# packmonitor.net
KiCad netlist of a schematic drawn in EAGLE
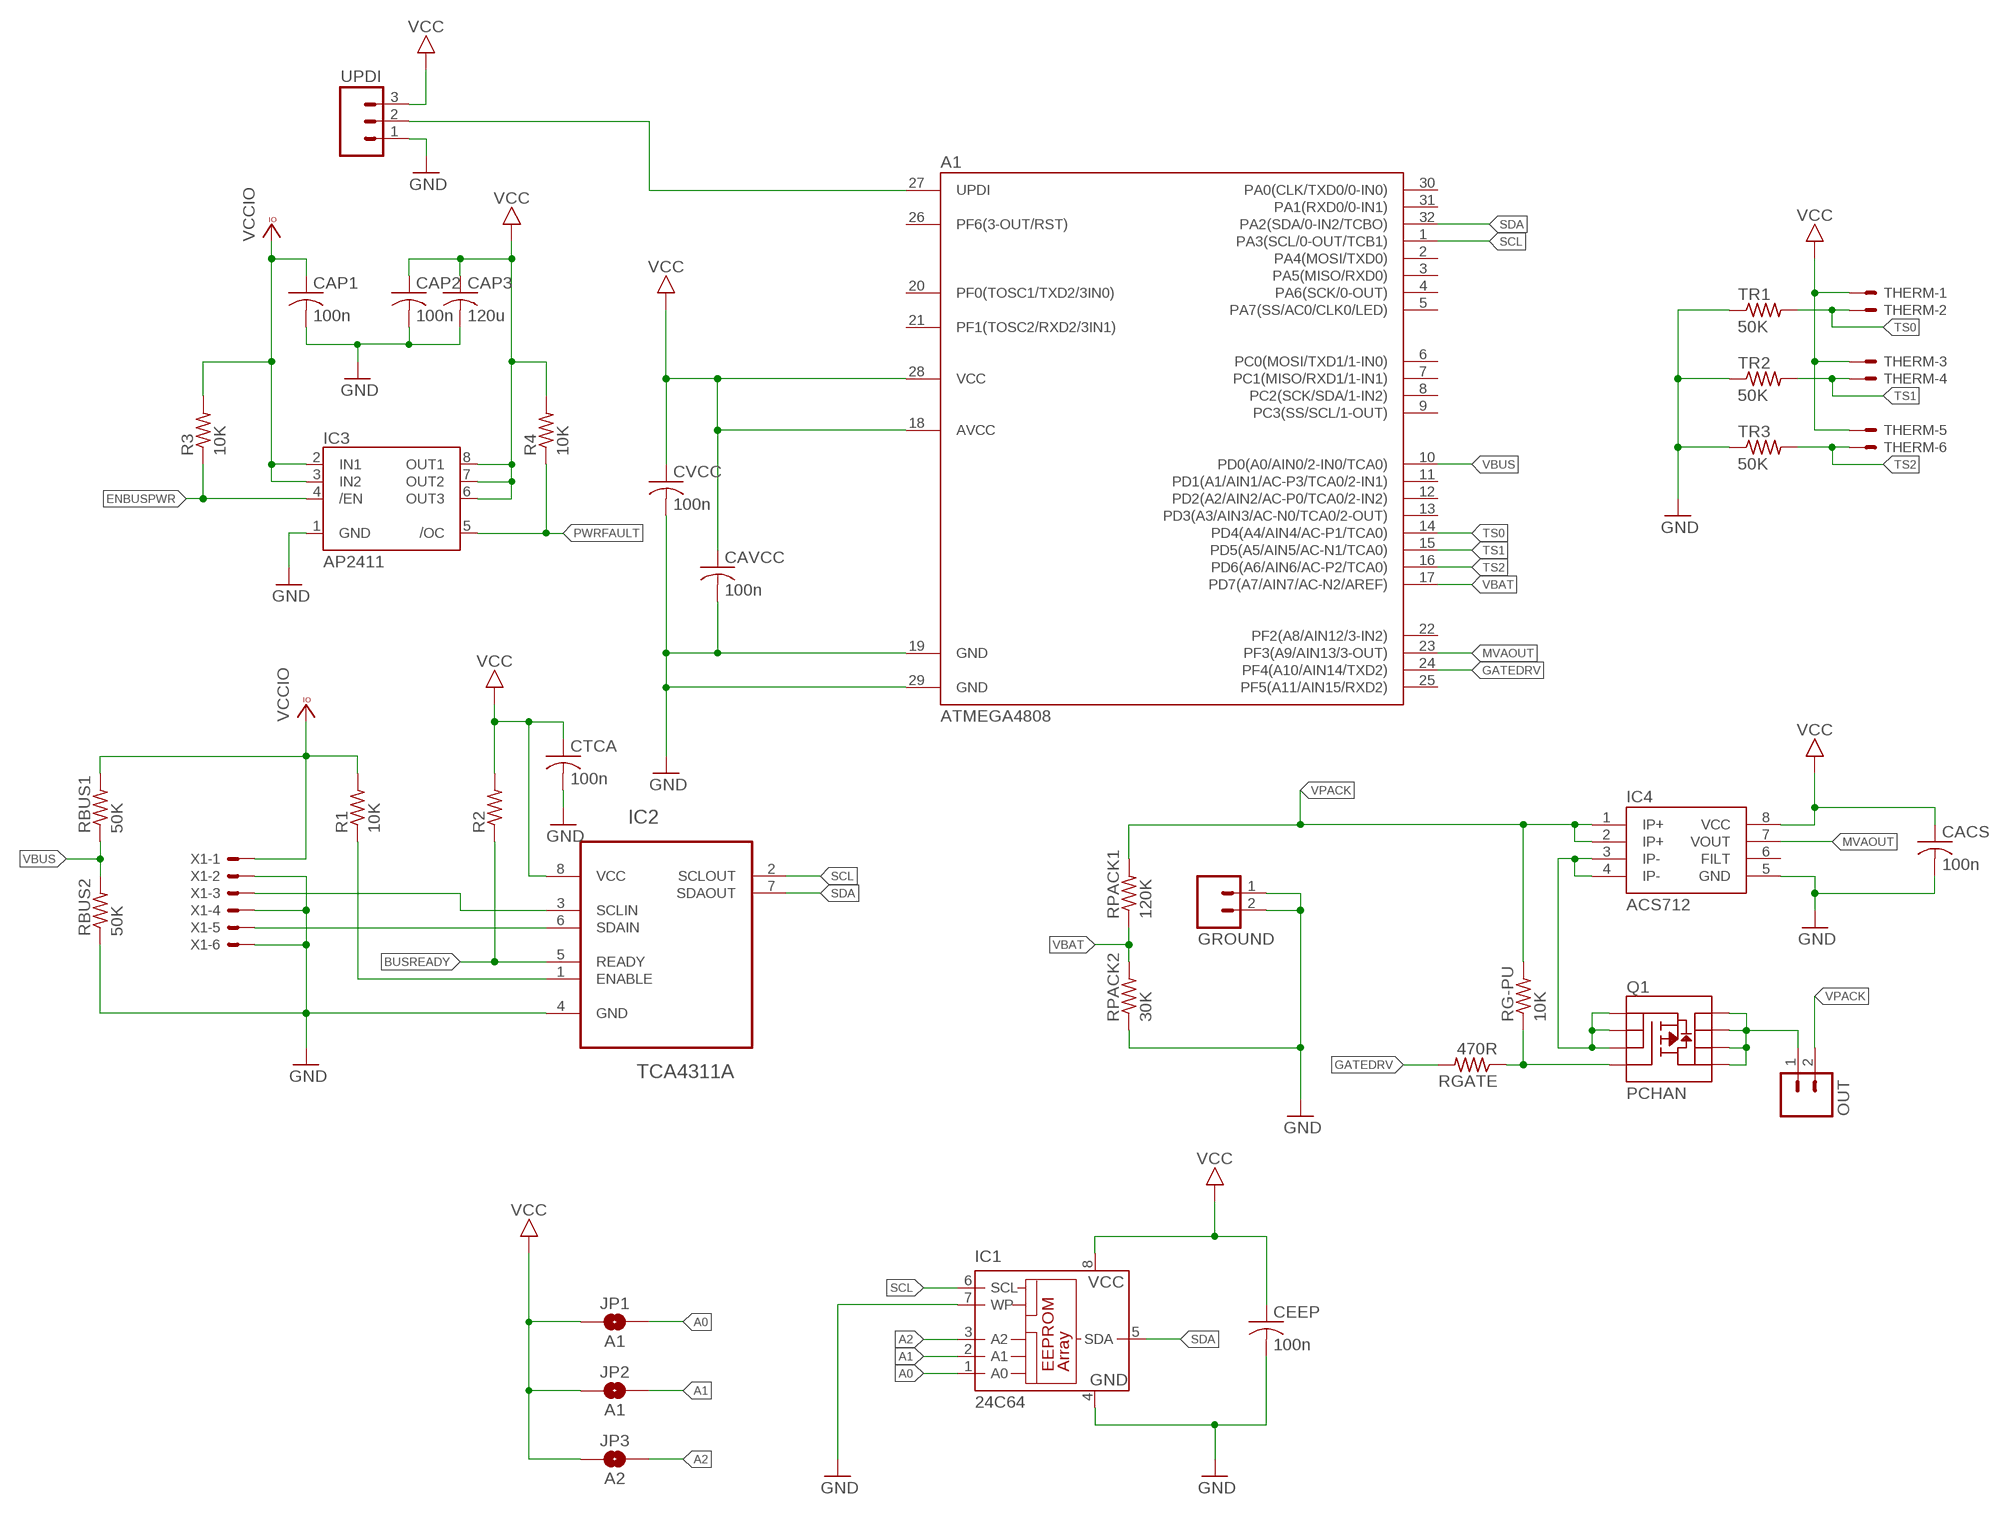
[diagram p0: schematic, sheet 1]

(export (version "E")
  (design (tool "Eeschema 10.0.6"))
  (components
    (comp (ref "A1")
      (value "ATMEGA4808")
      (footprint "eagle-import:TQFP32-08")
      (libsource (lib "eagle-import") (part "ATMEGA4808-TQFN32A"))
    )
    (comp (ref "CACS")
      (value "100n")
      (footprint "eagle-import:C0603")
      (libsource (lib "eagle-import") (part "C-USC0603"))
    )
    (comp (ref "CAP1")
      (value "100n")
      (footprint "eagle-import:C0603")
      (libsource (lib "eagle-import") (part "C-USC0603"))
    )
    (comp (ref "CAP2")
      (value "100n")
      (footprint "eagle-import:C0603")
      (libsource (lib "eagle-import") (part "C-USC0603"))
    )
    (comp (ref "CAP3")
      (value "120u")
      (footprint "eagle-import:C1206")
      (libsource (lib "eagle-import") (part "C-USC1206"))
    )
    (comp (ref "CAVCC")
      (value "100n")
      (footprint "eagle-import:C0603")
      (libsource (lib "eagle-import") (part "C-USC0603"))
    )
    (comp (ref "CEEP")
      (value "100n")
      (footprint "eagle-import:C0603")
      (libsource (lib "eagle-import") (part "C-USC0603"))
    )
    (comp (ref "CTCA")
      (value "100n")
      (footprint "eagle-import:C0603")
      (libsource (lib "eagle-import") (part "C-USC0603"))
    )
    (comp (ref "CVCC")
      (value "100n")
      (footprint "eagle-import:C0603")
      (libsource (lib "eagle-import") (part "C-USC0603"))
    )
    (comp (ref "GROUND")
      (value "M023.5MM")
      (footprint "eagle-import:SCREWTERMINAL-3.5MM-2")
      (libsource (lib "eagle-import") (part "M023.5MM"))
    )
    (comp (ref "IC1")
      (value "24C64")
      (footprint "eagle-import:SO-08")
      (libsource (lib "eagle-import") (part "24CSN04C"))
    )
    (comp (ref "IC2")
      (value "TCA4311A")
      (footprint "eagle-import:SOIC127P600X175-8N")
      (fields (field (name "MPN") "PCA9511AD,118"))
      (libsource (lib "eagle-import") (part "PCA9511AD,118"))
    )
    (comp (ref "IC3")
      (value "AP2411")
      (footprint "eagle-import:SO08")
      (libsource (lib "eagle-import") (part "TPS2041BD"))
    )
    (comp (ref "IC4")
      (value "ACS712")
      (footprint "eagle-import:SO08")
      (libsource (lib "eagle-import") (part "ACS712"))
    )
    (comp (ref "JP1")
      (value "A1")
      (footprint "eagle-import:SMT-JUMPER_2_NO_SILK")
      (libsource (lib "eagle-import") (part "JUMPER-SMT_2_NO_SILK"))
    )
    (comp (ref "JP2")
      (value "A1")
      (footprint "eagle-import:SMT-JUMPER_2_NO_SILK")
      (libsource (lib "eagle-import") (part "JUMPER-SMT_2_NO_SILK"))
    )
    (comp (ref "JP3")
      (value "A2")
      (footprint "eagle-import:SMT-JUMPER_2_NO_SILK")
      (libsource (lib "eagle-import") (part "JUMPER-SMT_2_NO_SILK"))
    )
    (comp (ref "OUT")
      (value "M023.5MM")
      (footprint "eagle-import:SCREWTERMINAL-3.5MM-2")
      (libsource (lib "eagle-import") (part "M023.5MM"))
    )
    (comp (ref "Q1")
      (value "PCHAN")
      (footprint "eagle-import:SO08")
      (libsource (lib "eagle-import") (part "MOSFET-PCHANNEL-SOIC8SOIC8"))
    )
    (comp (ref "R1")
      (value "10K")
      (footprint "eagle-import:R0603")
      (libsource (lib "eagle-import") (part "R-US_R0603"))
    )
    (comp (ref "R2")
      (value "R-US_R0603")
      (footprint "eagle-import:R0603")
      (libsource (lib "eagle-import") (part "R-US_R0603"))
    )
    (comp (ref "R3")
      (value "10K")
      (footprint "eagle-import:R0603")
      (libsource (lib "eagle-import") (part "R-US_R0603"))
    )
    (comp (ref "R4")
      (value "10K")
      (footprint "eagle-import:R0603")
      (libsource (lib "eagle-import") (part "R-US_R0603"))
    )
    (comp (ref "RBUS1")
      (value "50K")
      (footprint "eagle-import:R0805")
      (libsource (lib "eagle-import") (part "R-US_R0805"))
    )
    (comp (ref "RBUS2")
      (value "50K")
      (footprint "eagle-import:R0805")
      (libsource (lib "eagle-import") (part "R-US_R0805"))
    )
    (comp (ref "RG-PU")
      (value "10K")
      (footprint "eagle-import:R0603")
      (libsource (lib "eagle-import") (part "R-US_R0603"))
    )
    (comp (ref "RGATE")
      (value "470R")
      (footprint "eagle-import:R0603")
      (libsource (lib "eagle-import") (part "R-US_R0603"))
    )
    (comp (ref "RPACK1")
      (value "120K")
      (footprint "eagle-import:R0805")
      (libsource (lib "eagle-import") (part "R-US_R0805"))
    )
    (comp (ref "RPACK2")
      (value "30K")
      (footprint "eagle-import:R0805")
      (libsource (lib "eagle-import") (part "R-US_R0805"))
    )
    (comp (ref "THERM")
      (value "JST-XH-06-PIN-ROUND-PAD")
      (footprint "eagle-import:JST-XH-06-PACKAGE-ROUND-PAD")
      (libsource (lib "eagle-import") (part "JST-XH-06-PIN-ROUND-PAD"))
    )
    (comp (ref "TR1")
      (value "50K")
      (footprint "eagle-import:R0805")
      (libsource (lib "eagle-import") (part "R-US_R0805"))
    )
    (comp (ref "TR2")
      (value "50K")
      (footprint "eagle-import:R0805")
      (libsource (lib "eagle-import") (part "R-US_R0805"))
    )
    (comp (ref "TR3")
      (value "50K")
      (footprint "eagle-import:R0805")
      (libsource (lib "eagle-import") (part "R-US_R0805"))
    )
    (comp (ref "UPDI")
      (value "M03PTH")
      (footprint "eagle-import:1X03")
      (libsource (lib "eagle-import") (part "M03PTH"))
    )
    (comp (ref "X1")
      (value "JST-XH-06-PIN-LONG-PAD")
      (footprint "eagle-import:JST-XH-06-PACKAGE-LONG-PAD")
      (libsource (lib "eagle-import") (part "JST-XH-06-PIN-LONG-PAD"))
    )
  )
  (nets
    (net (code "1") (name "A0") (class "Default")
      (node (ref "IC1") (pin "1") (pinfunction "A0_1") (pintype "input"))
      (node (ref "JP1") (pin "2") (pinfunction "2_2") (pintype "passive"))
    )
    (net (code "2") (name "A1") (class "Default")
      (node (ref "IC1") (pin "2") (pinfunction "A1_2") (pintype "input"))
      (node (ref "JP2") (pin "2") (pinfunction "2_2") (pintype "passive"))
    )
    (net (code "3") (name "A2") (class "Default")
      (node (ref "IC1") (pin "3") (pinfunction "A2_3") (pintype "input"))
      (node (ref "JP3") (pin "2") (pinfunction "2_2") (pintype "passive"))
    )
    (net (code "4") (name "BUSREADY") (class "Default")
      (node (ref "IC2") (pin "5") (pinfunction "READY_5") (pintype "input"))
      (node (ref "R2") (pin "1") (pinfunction "1_1") (pintype "passive"))
    )
    (net (code "5") (name "ENBUSPWR") (class "Default")
      (node (ref "IC3") (pin "4") (pinfunction "/EN_4") (pintype "input"))
      (node (ref "R3") (pin "1") (pinfunction "1_1") (pintype "passive"))
    )
    (net (code "6") (name "GATEDRV") (class "Default")
      (node (ref "A1") (pin "24") (pinfunction "PF4(A10/AIN14/TXD2)_24") (pintype "bidirectional"))
      (node (ref "RGATE") (pin "2") (pinfunction "2_2") (pintype "passive"))
    )
    (net (code "7") (name "GND") (class "Default")
      (node (ref "A1") (pin "19") (pinfunction "GND_19") (pintype "power_in"))
      (node (ref "A1") (pin "29") (pinfunction "GND_29") (pintype "power_in"))
      (node (ref "CACS") (pin "2") (pinfunction "2_2") (pintype "passive"))
      (node (ref "CAP1") (pin "2") (pinfunction "2_2") (pintype "passive"))
      (node (ref "CAP2") (pin "2") (pinfunction "2_2") (pintype "passive"))
      (node (ref "CAP3") (pin "2") (pinfunction "2_2") (pintype "passive"))
      (node (ref "CAVCC") (pin "2") (pinfunction "2_2") (pintype "passive"))
      (node (ref "CEEP") (pin "2") (pinfunction "2_2") (pintype "passive"))
      (node (ref "CTCA") (pin "2") (pinfunction "2_2") (pintype "passive"))
      (node (ref "CVCC") (pin "2") (pinfunction "2_2") (pintype "passive"))
      (node (ref "GROUND") (pin "1") (pinfunction "1_1") (pintype "passive"))
      (node (ref "GROUND") (pin "2") (pinfunction "2_2") (pintype "passive"))
      (node (ref "IC1") (pin "4") (pinfunction "GND_4") (pintype "power_in"))
      (node (ref "IC1") (pin "7") (pinfunction "WP_7") (pintype "input"))
      (node (ref "IC2") (pin "4") (pinfunction "GND_4") (pintype "passive"))
      (node (ref "IC3") (pin "1") (pinfunction "GND_1") (pintype "power_in"))
      (node (ref "IC4") (pin "5") (pinfunction "GND_5") (pintype "bidirectional"))
      (node (ref "RBUS2") (pin "1") (pinfunction "1_1") (pintype "passive"))
      (node (ref "RPACK2") (pin "1") (pinfunction "1_1") (pintype "passive"))
      (node (ref "TR1") (pin "1") (pinfunction "1_1") (pintype "passive"))
      (node (ref "TR2") (pin "1") (pinfunction "1_1") (pintype "passive"))
      (node (ref "TR3") (pin "1") (pinfunction "1_1") (pintype "passive"))
      (node (ref "UPDI") (pin "1") (pinfunction "1_1") (pintype "passive"))
      (node (ref "X1") (pin "2") (pinfunction "S_2") (pintype "passive"))
      (node (ref "X1") (pin "4") (pinfunction "S_4") (pintype "passive"))
      (node (ref "X1") (pin "6") (pinfunction "S_6") (pintype "passive"))
    )
    (net (code "8") (name "MVAOUT") (class "Default")
      (node (ref "A1") (pin "23") (pinfunction "PF3(A9/AIN13/3-OUT)_23") (pintype "bidirectional"))
      (node (ref "IC4") (pin "7") (pinfunction "VOUT_7") (pintype "bidirectional"))
    )
    (net (code "9") (name "Net-(A1-UPDI)") (class "Default")
      (node (ref "A1") (pin "27") (pinfunction "UPDI_27") (pintype "bidirectional"))
      (node (ref "UPDI") (pin "2") (pinfunction "2_2") (pintype "passive"))
    )
    (net (code "10") (name "Net-(IC2-ENABLE)") (class "Default")
      (node (ref "IC2") (pin "1") (pinfunction "ENABLE_1") (pintype "input"))
      (node (ref "R1") (pin "1") (pinfunction "1_1") (pintype "passive"))
    )
    (net (code "11") (name "Net-(IC2-SCLIN)") (class "Default")
      (node (ref "IC2") (pin "3") (pinfunction "SCLIN_3") (pintype "input"))
      (node (ref "X1") (pin "3") (pinfunction "S_3") (pintype "passive"))
    )
    (net (code "12") (name "Net-(IC2-SDAIN)") (class "Default")
      (node (ref "IC2") (pin "6") (pinfunction "SDAIN_6") (pintype "input"))
      (node (ref "X1") (pin "5") (pinfunction "S_5") (pintype "passive"))
    )
    (net (code "13") (name "Net-(IC4-IP--Pad3)") (class "Default")
      (node (ref "IC4") (pin "3") (pinfunction "IP-_3") (pintype "bidirectional"))
      (node (ref "IC4") (pin "4") (pinfunction "IP-_4") (pintype "bidirectional"))
      (node (ref "Q1") (pin "1") (pinfunction "S_1") (pintype "bidirectional"))
      (node (ref "Q1") (pin "2") (pinfunction "S_2") (pintype "bidirectional"))
      (node (ref "Q1") (pin "3") (pinfunction "S_3") (pintype "bidirectional"))
    )
    (net (code "14") (name "Net-(OUT-Pad1)") (class "Default")
      (node (ref "OUT") (pin "1") (pinfunction "1_1") (pintype "passive"))
      (node (ref "Q1") (pin "5") (pinfunction "D_5") (pintype "bidirectional"))
      (node (ref "Q1") (pin "6") (pinfunction "D_6") (pintype "bidirectional"))
      (node (ref "Q1") (pin "7") (pinfunction "D_7") (pintype "bidirectional"))
      (node (ref "Q1") (pin "8") (pinfunction "D_8") (pintype "bidirectional"))
    )
    (net (code "15") (name "Net-(Q1-G)") (class "Default")
      (node (ref "Q1") (pin "4") (pinfunction "G_4") (pintype "bidirectional"))
      (node (ref "RG-PU") (pin "1") (pinfunction "1_1") (pintype "passive"))
      (node (ref "RGATE") (pin "1") (pinfunction "1_1") (pintype "passive"))
    )
    (net (code "16") (name "PWRFAULT") (class "Default")
      (node (ref "IC3") (pin "5") (pinfunction "/OC_5") (pintype "open_collector"))
      (node (ref "R4") (pin "1") (pinfunction "1_1") (pintype "passive"))
    )
    (net (code "17") (name "SCL") (class "Default")
      (node (ref "A1") (pin "1") (pinfunction "PA3(SCL/0-OUT/TCB1)_1") (pintype "bidirectional"))
      (node (ref "IC1") (pin "6") (pinfunction "SCL_6") (pintype "input"))
      (node (ref "IC2") (pin "2") (pinfunction "SCLOUT_2") (pintype "output"))
    )
    (net (code "18") (name "SDA") (class "Default")
      (node (ref "A1") (pin "32") (pinfunction "PA2(SDA/0-IN2/TCBO)_32") (pintype "bidirectional"))
      (node (ref "IC1") (pin "5") (pinfunction "SDA_5") (pintype "bidirectional"))
      (node (ref "IC2") (pin "7") (pinfunction "SDAOUT_7") (pintype "output"))
    )
    (net (code "19") (name "TS0") (class "Default")
      (node (ref "A1") (pin "14") (pinfunction "PD4(A4/AIN4/AC-P1/TCA0)_14") (pintype "bidirectional"))
      (node (ref "THERM") (pin "2") (pinfunction "S_2") (pintype "passive"))
      (node (ref "TR1") (pin "2") (pinfunction "2_2") (pintype "passive"))
    )
    (net (code "20") (name "TS1") (class "Default")
      (node (ref "A1") (pin "15") (pinfunction "PD5(A5/AIN5/AC-N1/TCA0)_15") (pintype "bidirectional"))
      (node (ref "THERM") (pin "4") (pinfunction "S_4") (pintype "passive"))
      (node (ref "TR2") (pin "2") (pinfunction "2_2") (pintype "passive"))
    )
    (net (code "21") (name "TS2") (class "Default")
      (node (ref "A1") (pin "16") (pinfunction "PD6(A6/AIN6/AC-P2/TCA0)_16") (pintype "bidirectional"))
      (node (ref "THERM") (pin "6") (pinfunction "S_6") (pintype "passive"))
      (node (ref "TR3") (pin "2") (pinfunction "2_2") (pintype "passive"))
    )
    (net (code "22") (name "VBAT") (class "Default")
      (node (ref "A1") (pin "17") (pinfunction "PD7(A7/AIN7/AC-N2/AREF)_17") (pintype "bidirectional"))
      (node (ref "RPACK1") (pin "1") (pinfunction "1_1") (pintype "passive"))
      (node (ref "RPACK2") (pin "2") (pinfunction "2_2") (pintype "passive"))
    )
    (net (code "23") (name "VBUS") (class "Default")
      (node (ref "A1") (pin "10") (pinfunction "PD0(A0/AIN0/2-IN0/TCA0)_10") (pintype "bidirectional"))
      (node (ref "RBUS1") (pin "1") (pinfunction "1_1") (pintype "passive"))
      (node (ref "RBUS2") (pin "2") (pinfunction "2_2") (pintype "passive"))
    )
    (net (code "24") (name "VCC") (class "Default")
      (node (ref "A1") (pin "18") (pinfunction "AVCC_18") (pintype "passive"))
      (node (ref "A1") (pin "28") (pinfunction "VCC_28") (pintype "power_in"))
      (node (ref "CACS") (pin "1") (pinfunction "1_1") (pintype "passive"))
      (node (ref "CAP2") (pin "1") (pinfunction "1_1") (pintype "passive"))
      (node (ref "CAP3") (pin "1") (pinfunction "1_1") (pintype "passive"))
      (node (ref "CAVCC") (pin "1") (pinfunction "1_1") (pintype "passive"))
      (node (ref "CEEP") (pin "1") (pinfunction "1_1") (pintype "passive"))
      (node (ref "CTCA") (pin "1") (pinfunction "1_1") (pintype "passive"))
      (node (ref "CVCC") (pin "1") (pinfunction "1_1") (pintype "passive"))
      (node (ref "IC1") (pin "8") (pinfunction "VCC_8") (pintype "power_in"))
      (node (ref "IC2") (pin "8") (pinfunction "VCC_8") (pintype "power_in"))
      (node (ref "IC3") (pin "6") (pinfunction "OUT3_6") (pintype "power_in"))
      (node (ref "IC3") (pin "7") (pinfunction "OUT2_7") (pintype "power_in"))
      (node (ref "IC3") (pin "8") (pinfunction "OUT1_8") (pintype "power_in"))
      (node (ref "IC4") (pin "8") (pinfunction "VCC_8") (pintype "bidirectional"))
      (node (ref "JP1") (pin "1") (pinfunction "1_1") (pintype "passive"))
      (node (ref "JP2") (pin "1") (pinfunction "1_1") (pintype "passive"))
      (node (ref "JP3") (pin "1") (pinfunction "1_1") (pintype "passive"))
      (node (ref "R2") (pin "2") (pinfunction "2_2") (pintype "passive"))
      (node (ref "R4") (pin "2") (pinfunction "2_2") (pintype "passive"))
      (node (ref "THERM") (pin "1") (pinfunction "S_1") (pintype "passive"))
      (node (ref "THERM") (pin "3") (pinfunction "S_3") (pintype "passive"))
      (node (ref "THERM") (pin "5") (pinfunction "S_5") (pintype "passive"))
      (node (ref "UPDI") (pin "3") (pinfunction "3_3") (pintype "passive"))
    )
    (net (code "25") (name "VCCIO") (class "Default")
      (node (ref "CAP1") (pin "1") (pinfunction "1_1") (pintype "passive"))
      (node (ref "IC3") (pin "2") (pinfunction "IN1_2") (pintype "power_in"))
      (node (ref "IC3") (pin "3") (pinfunction "IN2_3") (pintype "power_in"))
      (node (ref "R1") (pin "2") (pinfunction "2_2") (pintype "passive"))
      (node (ref "R3") (pin "2") (pinfunction "2_2") (pintype "passive"))
      (node (ref "RBUS1") (pin "2") (pinfunction "2_2") (pintype "passive"))
      (node (ref "X1") (pin "1") (pinfunction "S_1") (pintype "passive"))
    )
    (net (code "26") (name "VPACK") (class "Default")
      (node (ref "IC4") (pin "1") (pinfunction "IP+_1") (pintype "bidirectional"))
      (node (ref "IC4") (pin "2") (pinfunction "IP+_2") (pintype "bidirectional"))
      (node (ref "OUT") (pin "2") (pinfunction "2_2") (pintype "passive"))
      (node (ref "RG-PU") (pin "2") (pinfunction "2_2") (pintype "passive"))
      (node (ref "RPACK1") (pin "2") (pinfunction "2_2") (pintype "passive"))
    )
    (net (code "27") (name "unconnected-(A1-PA0(CLK{slash}TXD0{slash}0-IN0)-Pad30)") (class "Default")
      (node (ref "A1") (pin "30") (pinfunction "PA0(CLK/TXD0/0-IN0)_30") (pintype "bidirectional"))
    )
    (net (code "28") (name "unconnected-(A1-PA1(RXD0{slash}0-IN1)-Pad31)") (class "Default")
      (node (ref "A1") (pin "31") (pinfunction "PA1(RXD0/0-IN1)_31") (pintype "bidirectional"))
    )
    (net (code "29") (name "unconnected-(A1-PA4(MOSI{slash}TXD0)-Pad2)") (class "Default")
      (node (ref "A1") (pin "2") (pinfunction "PA4(MOSI/TXD0)_2") (pintype "bidirectional"))
    )
    (net (code "30") (name "unconnected-(A1-PA5(MISO{slash}RXD0)-Pad3)") (class "Default")
      (node (ref "A1") (pin "3") (pinfunction "PA5(MISO/RXD0)_3") (pintype "bidirectional"))
    )
    (net (code "31") (name "unconnected-(A1-PA6(SCK{slash}0-OUT)-Pad4)") (class "Default")
      (node (ref "A1") (pin "4") (pinfunction "PA6(SCK/0-OUT)_4") (pintype "bidirectional"))
    )
    (net (code "32") (name "unconnected-(A1-PA7(SS{slash}AC0{slash}CLK0{slash}LED)-Pad5)") (class "Default")
      (node (ref "A1") (pin "5") (pinfunction "PA7(SS/AC0/CLK0/LED)_5") (pintype "bidirectional"))
    )
    (net (code "33") (name "unconnected-(A1-PC0(MOSI{slash}TXD1{slash}1-IN0)-Pad6)") (class "Default")
      (node (ref "A1") (pin "6") (pinfunction "PC0(MOSI/TXD1/1-IN0)_6") (pintype "bidirectional"))
    )
    (net (code "34") (name "unconnected-(A1-PC1(MISO{slash}RXD1{slash}1-IN1)-Pad7)") (class "Default")
      (node (ref "A1") (pin "7") (pinfunction "PC1(MISO/RXD1/1-IN1)_7") (pintype "bidirectional"))
    )
    (net (code "35") (name "unconnected-(A1-PC2(SCK{slash}SDA{slash}1-IN2)-Pad8)") (class "Default")
      (node (ref "A1") (pin "8") (pinfunction "PC2(SCK/SDA/1-IN2)_8") (pintype "bidirectional"))
    )
    (net (code "36") (name "unconnected-(A1-PC3(SS{slash}SCL{slash}1-OUT)-Pad9)") (class "Default")
      (node (ref "A1") (pin "9") (pinfunction "PC3(SS/SCL/1-OUT)_9") (pintype "bidirectional"))
    )
    (net (code "37") (name "unconnected-(A1-PD1(A1{slash}AIN1{slash}AC-P3{slash}TCA0{slash}2-IN1)-Pad11)") (class "Default")
      (node (ref "A1") (pin "11") (pinfunction "PD1(A1/AIN1/AC-P3/TCA0/2-IN1)_11") (pintype "bidirectional"))
    )
    (net (code "38") (name "unconnected-(A1-PD2(A2{slash}AIN2{slash}AC-P0{slash}TCA0{slash}2-IN2)-Pad12)") (class "Default")
      (node (ref "A1") (pin "12") (pinfunction "PD2(A2/AIN2/AC-P0/TCA0/2-IN2)_12") (pintype "bidirectional"))
    )
    (net (code "39") (name "unconnected-(A1-PD3(A3{slash}AIN3{slash}AC-N0{slash}TCA0{slash}2-OUT)-Pad13)") (class "Default")
      (node (ref "A1") (pin "13") (pinfunction "PD3(A3/AIN3/AC-N0/TCA0/2-OUT)_13") (pintype "bidirectional"))
    )
    (net (code "40") (name "unconnected-(A1-PF0(TOSC1{slash}TXD2{slash}3IN0)-Pad20)") (class "Default")
      (node (ref "A1") (pin "20") (pinfunction "PF0(TOSC1/TXD2/3IN0)_20") (pintype "bidirectional"))
    )
    (net (code "41") (name "unconnected-(A1-PF1(TOSC2{slash}RXD2{slash}3IN1)-Pad21)") (class "Default")
      (node (ref "A1") (pin "21") (pinfunction "PF1(TOSC2/RXD2/3IN1)_21") (pintype "bidirectional"))
    )
    (net (code "42") (name "unconnected-(A1-PF2(A8{slash}AIN12{slash}3-IN2)-Pad22)") (class "Default")
      (node (ref "A1") (pin "22") (pinfunction "PF2(A8/AIN12/3-IN2)_22") (pintype "bidirectional"))
    )
    (net (code "43") (name "unconnected-(A1-PF5(A11{slash}AIN15{slash}RXD2)-Pad25)") (class "Default")
      (node (ref "A1") (pin "25") (pinfunction "PF5(A11/AIN15/RXD2)_25") (pintype "bidirectional"))
    )
    (net (code "44") (name "unconnected-(A1-PF6(3-OUT{slash}RST)-Pad26)") (class "Default")
      (node (ref "A1") (pin "26") (pinfunction "PF6(3-OUT/RST)_26") (pintype "bidirectional"))
    )
    (net (code "45") (name "unconnected-(IC4-FILT-Pad6)") (class "Default")
      (node (ref "IC4") (pin "6") (pinfunction "FILT_6") (pintype "bidirectional"))
    )
  )
)
